# MOTOR_CONTROL.net
KiCad netlist of a schematic drawn in Altium Designer
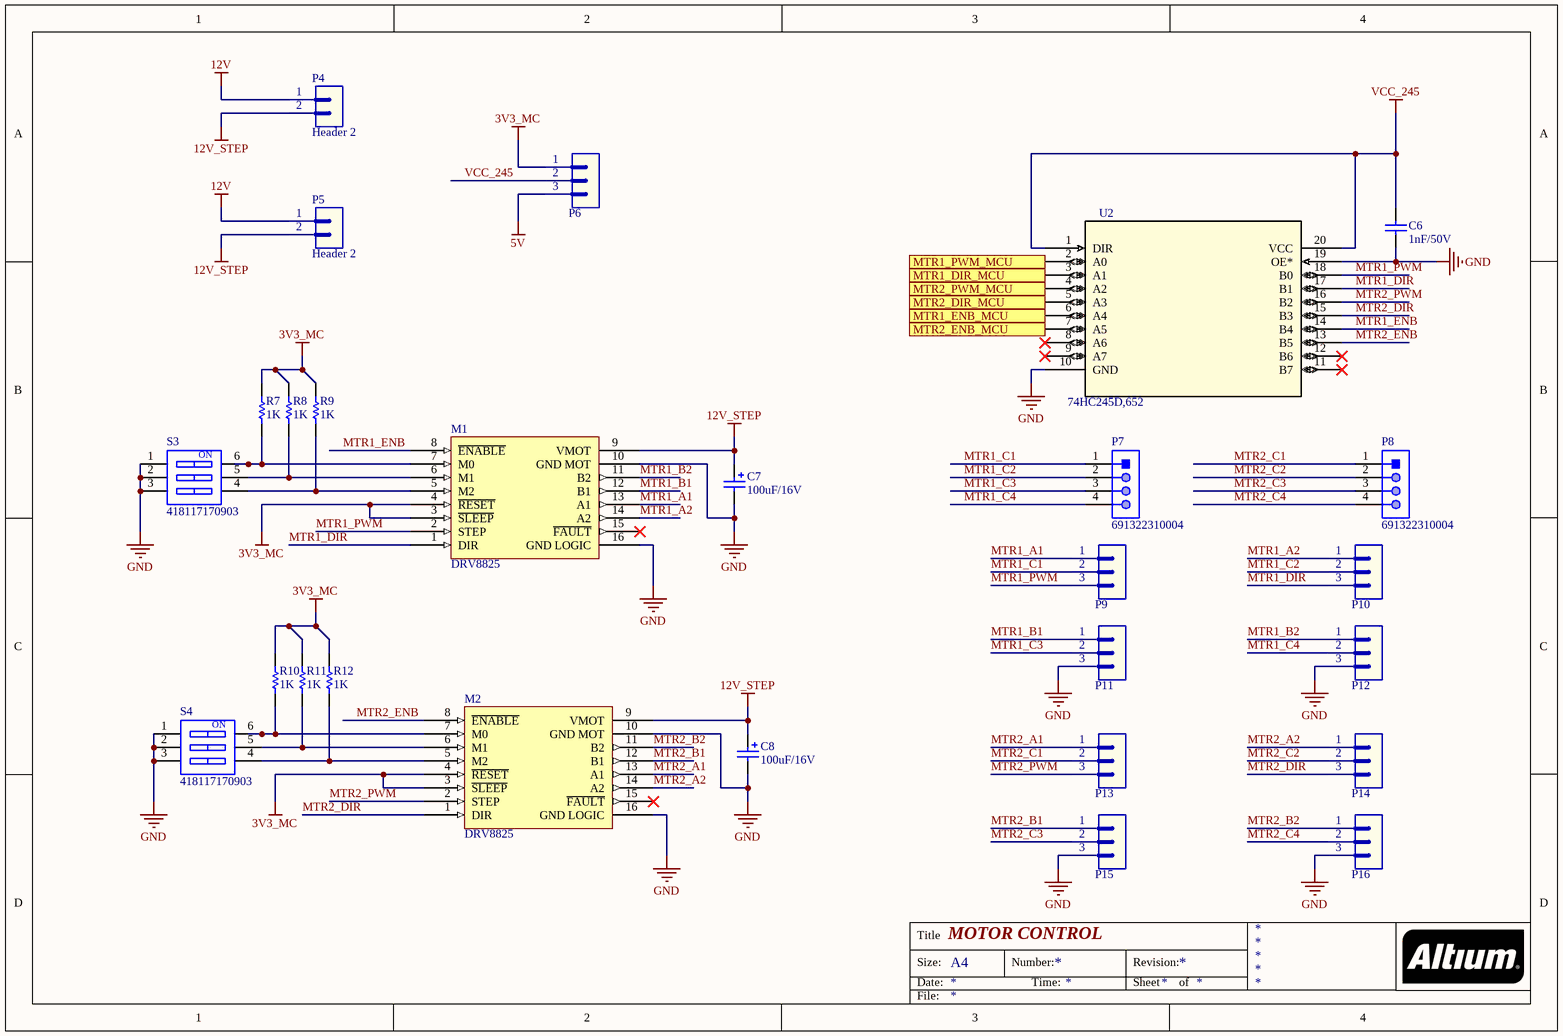
[diagram p0: MOTOR_CONTROL.SchDoc]

(export (version "E")
  (design (tool "Eeschema 10.0.6"))
  (components
    (comp (ref "C6")
      (value "1nF/50V")
      (footprint "CAP-SM-0805")
      (description "CAP CER 1000PF 100V X7R 0805")
      (fields
        (field (name "MANUFACTURER") "Johanson Dielectrics Inc.")
        (field (name "MANUFACTURER PART NUMBER") "101X15W102MV4E")
      )
      (libsource (lib "PIF_ROBOT") (part "Cap-1nF-50V-0805"))
    )
    (comp (ref "C7")
      (value "100uF/16V")
      (footprint "CAP_SM_TAN")
      (fields
        (field (name "MANUFACTURER") "Nichicon")
        (field (name "MANUFACTURER PART NUMBER") "UWX1C101MCL1GB")
        (field (name "Comment") "TAJB107M006RNJ")
      )
      (libsource (lib "PIF_ROBOT") (part "Cap-Tan-100uF-16V"))
    )
    (comp (ref "C8")
      (value "100uF/16V")
      (footprint "CAP_SM_TAN")
      (fields
        (field (name "MANUFACTURER") "Nichicon")
        (field (name "MANUFACTURER PART NUMBER") "UWX1C101MCL1GB")
        (field (name "Comment") "TAJB107M006RNJ")
      )
      (libsource (lib "PIF_ROBOT") (part "Cap-Tan-100uF-16V"))
    )
    (comp (ref "M1") (value "DRV8825") (footprint "DRV8825") (libsource (lib "PIF_ROBOT") (part "DRV8825")))
    (comp (ref "M2") (value "DRV8825") (footprint "DRV8825") (libsource (lib "PIF_ROBOT") (part "DRV8825")))
    (comp (ref "P4")
      (value "Header 2")
      (footprint "JP2")
      (description "Header, 2-Pin")
      (fields (field (name "PUBLISHER") "Altium Limited"))
      (libsource (lib "PIF_ROBOT") (part "Header 2"))
    )
    (comp (ref "P5")
      (value "Header 2")
      (footprint "JP2")
      (description "Header, 2-Pin")
      (fields (field (name "PUBLISHER") "Altium Limited"))
      (libsource (lib "PIF_ROBOT") (part "Header 2"))
    )
    (comp (ref "P6")
      (value "Header 3")
      (footprint "JP3")
      (description "Header, 3-Pin")
      (fields (field (name "PUBLISHER") "Altium Limited"))
      (libsource (lib "PIF_ROBOT") (part "Header 3"))
    )
    (comp (ref "P7")
      (value "691322310004")
      (footprint "691322310004")
      (description "WR-TBL Serie 322 Horizontal PCB Header, Pluggable, pitch 3.81mm, 4p")
      (fields (field (name "PUBLISHER") "Wurth Elektronik"))
      (libsource (lib "PIF_ROBOT") (part "691322310004"))
    )
    (comp (ref "P8")
      (value "691322310004")
      (footprint "691322310004")
      (description "WR-TBL Serie 322 Horizontal PCB Header, Pluggable, pitch 3.81mm, 4p")
      (fields (field (name "PUBLISHER") "Wurth Elektronik"))
      (libsource (lib "PIF_ROBOT") (part "691322310004"))
    )
    (comp (ref "P9")
      (value "Header 3")
      (footprint "JP3")
      (description "Header, 3-Pin")
      (fields (field (name "PUBLISHER") "Altium Limited"))
      (libsource (lib "PIF_ROBOT") (part "Header 3"))
    )
    (comp (ref "P10")
      (value "Header 3")
      (footprint "JP3")
      (description "Header, 3-Pin")
      (fields (field (name "PUBLISHER") "Altium Limited"))
      (libsource (lib "PIF_ROBOT") (part "Header 3"))
    )
    (comp (ref "P11")
      (value "Header 3")
      (footprint "JP3")
      (description "Header, 3-Pin")
      (fields (field (name "PUBLISHER") "Altium Limited"))
      (libsource (lib "PIF_ROBOT") (part "Header 3"))
    )
    (comp (ref "P12")
      (value "Header 3")
      (footprint "JP3")
      (description "Header, 3-Pin")
      (fields (field (name "PUBLISHER") "Altium Limited"))
      (libsource (lib "PIF_ROBOT") (part "Header 3"))
    )
    (comp (ref "P13")
      (value "Header 3")
      (footprint "JP3")
      (description "Header, 3-Pin")
      (fields (field (name "PUBLISHER") "Altium Limited"))
      (libsource (lib "PIF_ROBOT") (part "Header 3"))
    )
    (comp (ref "P14")
      (value "Header 3")
      (footprint "JP3")
      (description "Header, 3-Pin")
      (fields (field (name "PUBLISHER") "Altium Limited"))
      (libsource (lib "PIF_ROBOT") (part "Header 3"))
    )
    (comp (ref "P15")
      (value "Header 3")
      (footprint "JP3")
      (description "Header, 3-Pin")
      (fields (field (name "PUBLISHER") "Altium Limited"))
      (libsource (lib "PIF_ROBOT") (part "Header 3"))
    )
    (comp (ref "P16")
      (value "Header 3")
      (footprint "JP3")
      (description "Header, 3-Pin")
      (fields (field (name "PUBLISHER") "Altium Limited"))
      (libsource (lib "PIF_ROBOT") (part "Header 3"))
    )
    (comp (ref "R7")
      (value "1K")
      (footprint "RES-SM-0805")
      (description "RES 0 OHM JUMPER 0805")
      (fields
        (field (name "MANUFACTURER") "Vishay Dale")
        (field (name "MANUFACTURER PART NUMBER") "WSL080500000ZEA9")
      )
      (libsource (lib "PIF_ROBOT") (part "Res-0-0805"))
    )
    (comp (ref "R8")
      (value "1K")
      (footprint "RES-SM-0805")
      (description "RES 0 OHM JUMPER 0805")
      (fields
        (field (name "MANUFACTURER") "Vishay Dale")
        (field (name "MANUFACTURER PART NUMBER") "WSL080500000ZEA9")
      )
      (libsource (lib "PIF_ROBOT") (part "Res-0-0805"))
    )
    (comp (ref "R9")
      (value "1K")
      (footprint "RES-SM-0805")
      (description "RES 0 OHM JUMPER 0805")
      (fields
        (field (name "MANUFACTURER") "Vishay Dale")
        (field (name "MANUFACTURER PART NUMBER") "WSL080500000ZEA9")
      )
      (libsource (lib "PIF_ROBOT") (part "Res-0-0805"))
    )
    (comp (ref "R10")
      (value "1K")
      (footprint "RES-SM-0805")
      (description "RES 0 OHM JUMPER 0805")
      (fields
        (field (name "MANUFACTURER") "Vishay Dale")
        (field (name "MANUFACTURER PART NUMBER") "WSL080500000ZEA9")
      )
      (libsource (lib "PIF_ROBOT") (part "Res-0-0805"))
    )
    (comp (ref "R11")
      (value "1K")
      (footprint "RES-SM-0805")
      (description "RES 0 OHM JUMPER 0805")
      (fields
        (field (name "MANUFACTURER") "Vishay Dale")
        (field (name "MANUFACTURER PART NUMBER") "WSL080500000ZEA9")
      )
      (libsource (lib "PIF_ROBOT") (part "Res-0-0805"))
    )
    (comp (ref "R12")
      (value "1K")
      (footprint "RES-SM-0805")
      (description "RES 0 OHM JUMPER 0805")
      (fields
        (field (name "MANUFACTURER") "Vishay Dale")
        (field (name "MANUFACTURER PART NUMBER") "WSL080500000ZEA9")
      )
      (libsource (lib "PIF_ROBOT") (part "Res-0-0805"))
    )
    (comp (ref "S3")
      (value "418117170903")
      (footprint "418117170903")
      (description "WS-DITV Compact THT Dip Switch, Flat Actuator, pitch 2.54mm, 3p")
      (fields (field (name "PUBLISHER") "Wurth Elektronik"))
      (libsource (lib "PIF_ROBOT") (part "418117170903"))
    )
    (comp (ref "S4")
      (value "418117170903")
      (footprint "418117170903")
      (description "WS-DITV Compact THT Dip Switch, Flat Actuator, pitch 2.54mm, 3p")
      (fields (field (name "PUBLISHER") "Wurth Elektronik"))
      (libsource (lib "PIF_ROBOT") (part "418117170903"))
    )
    (comp (ref "U2")
      (value "74HC245D,652")
      (footprint "74hc245d")
      (description "No Description Available")
      (fields (field (name "COPYRIGHT") "Copyright (C) 2016 Accelerated Designs. All rights reserved"))
      (libsource (lib "PIF_ROBOT") (part "74HC245D,652"))
    )
  )
  (nets
    (net (code "1") (name "/MTR1_A1") (class "Default")
      (node (ref "M1") (pin "13") (pinfunction "A1_13") (pintype "output"))
      (node (ref "P9") (pin "1") (pinfunction "1_1") (pintype "passive"))
    )
    (net (code "2") (name "/MTR1_A2") (class "Default")
      (node (ref "M1") (pin "14") (pinfunction "A2_14") (pintype "output"))
      (node (ref "P10") (pin "1") (pinfunction "1_1") (pintype "passive"))
    )
    (net (code "3") (name "/MTR1_B1") (class "Default")
      (node (ref "M1") (pin "12") (pinfunction "B1_12") (pintype "output"))
      (node (ref "P11") (pin "1") (pinfunction "1_1") (pintype "passive"))
    )
    (net (code "4") (name "/MTR1_B2") (class "Default")
      (node (ref "M1") (pin "11") (pinfunction "B2_11") (pintype "output"))
      (node (ref "P12") (pin "1") (pinfunction "1_1") (pintype "passive"))
    )
    (net (code "5") (name "/MTR1_C1") (class "Default")
      (node (ref "P7") (pin "1") (pinfunction "1_1") (pintype "passive"))
      (node (ref "P9") (pin "2") (pinfunction "2_2") (pintype "passive"))
    )
    (net (code "6") (name "/MTR1_C2") (class "Default")
      (node (ref "P10") (pin "2") (pinfunction "2_2") (pintype "passive"))
      (node (ref "P7") (pin "2") (pinfunction "2_2") (pintype "passive"))
    )
    (net (code "7") (name "/MTR1_C3") (class "Default")
      (node (ref "P11") (pin "2") (pinfunction "2_2") (pintype "passive"))
      (node (ref "P7") (pin "3") (pinfunction "3_3") (pintype "passive"))
    )
    (net (code "8") (name "/MTR1_C4") (class "Default")
      (node (ref "P12") (pin "2") (pinfunction "2_2") (pintype "passive"))
      (node (ref "P7") (pin "4") (pinfunction "4_4") (pintype "passive"))
    )
    (net (code "9") (name "/MTR1_DIR") (class "Default")
      (node (ref "M1") (pin "1") (pinfunction "DIR_1") (pintype "input"))
      (node (ref "P10") (pin "3") (pinfunction "3_3") (pintype "passive"))
      (node (ref "U2") (pin "17") (pinfunction "B1_17") (pintype "bidirectional"))
    )
    (net (code "10") (name "/MTR1_DIR_MCU") (class "Default")
      (node (ref "U2") (pin "3") (pinfunction "A1_3") (pintype "bidirectional"))
    )
    (net (code "11") (name "/MTR1_ENB") (class "Default")
      (node (ref "M1") (pin "8") (pinfunction "~{ENABLE}_8") (pintype "input"))
      (node (ref "U2") (pin "14") (pinfunction "B4_14") (pintype "bidirectional"))
    )
    (net (code "12") (name "/MTR1_ENB_MCU") (class "Default")
      (node (ref "U2") (pin "6") (pinfunction "A4_6") (pintype "bidirectional"))
    )
    (net (code "13") (name "/MTR1_PWM") (class "Default")
      (node (ref "M1") (pin "2") (pinfunction "STEP_2") (pintype "input"))
      (node (ref "P9") (pin "3") (pinfunction "3_3") (pintype "passive"))
      (node (ref "U2") (pin "18") (pinfunction "B0_18") (pintype "bidirectional"))
    )
    (net (code "14") (name "/MTR1_PWM_MCU") (class "Default")
      (node (ref "U2") (pin "2") (pinfunction "A0_2") (pintype "bidirectional"))
    )
    (net (code "15") (name "/MTR2_A1") (class "Default")
      (node (ref "M2") (pin "13") (pinfunction "A1_13") (pintype "output"))
      (node (ref "P13") (pin "1") (pinfunction "1_1") (pintype "passive"))
    )
    (net (code "16") (name "/MTR2_A2") (class "Default")
      (node (ref "M2") (pin "14") (pinfunction "A2_14") (pintype "output"))
      (node (ref "P14") (pin "1") (pinfunction "1_1") (pintype "passive"))
    )
    (net (code "17") (name "/MTR2_B1") (class "Default")
      (node (ref "M2") (pin "12") (pinfunction "B1_12") (pintype "output"))
      (node (ref "P15") (pin "1") (pinfunction "1_1") (pintype "passive"))
    )
    (net (code "18") (name "/MTR2_B2") (class "Default")
      (node (ref "M2") (pin "11") (pinfunction "B2_11") (pintype "output"))
      (node (ref "P16") (pin "1") (pinfunction "1_1") (pintype "passive"))
    )
    (net (code "19") (name "/MTR2_C1") (class "Default")
      (node (ref "P13") (pin "2") (pinfunction "2_2") (pintype "passive"))
      (node (ref "P8") (pin "1") (pinfunction "1_1") (pintype "passive"))
    )
    (net (code "20") (name "/MTR2_C2") (class "Default")
      (node (ref "P14") (pin "2") (pinfunction "2_2") (pintype "passive"))
      (node (ref "P8") (pin "2") (pinfunction "2_2") (pintype "passive"))
    )
    (net (code "21") (name "/MTR2_C3") (class "Default")
      (node (ref "P15") (pin "2") (pinfunction "2_2") (pintype "passive"))
      (node (ref "P8") (pin "3") (pinfunction "3_3") (pintype "passive"))
    )
    (net (code "22") (name "/MTR2_C4") (class "Default")
      (node (ref "P16") (pin "2") (pinfunction "2_2") (pintype "passive"))
      (node (ref "P8") (pin "4") (pinfunction "4_4") (pintype "passive"))
    )
    (net (code "23") (name "/MTR2_DIR") (class "Default")
      (node (ref "M2") (pin "1") (pinfunction "DIR_1") (pintype "input"))
      (node (ref "P14") (pin "3") (pinfunction "3_3") (pintype "passive"))
      (node (ref "U2") (pin "15") (pinfunction "B3_15") (pintype "bidirectional"))
    )
    (net (code "24") (name "/MTR2_DIR_MCU") (class "Default")
      (node (ref "U2") (pin "5") (pinfunction "A3_5") (pintype "bidirectional"))
    )
    (net (code "25") (name "/MTR2_ENB") (class "Default")
      (node (ref "M2") (pin "8") (pinfunction "~{ENABLE}_8") (pintype "input"))
      (node (ref "U2") (pin "13") (pinfunction "B5_13") (pintype "bidirectional"))
    )
    (net (code "26") (name "/MTR2_ENB_MCU") (class "Default")
      (node (ref "U2") (pin "7") (pinfunction "A5_7") (pintype "bidirectional"))
    )
    (net (code "27") (name "/MTR2_PWM") (class "Default")
      (node (ref "M2") (pin "2") (pinfunction "STEP_2") (pintype "input"))
      (node (ref "P13") (pin "3") (pinfunction "3_3") (pintype "passive"))
      (node (ref "U2") (pin "16") (pinfunction "B2_16") (pintype "bidirectional"))
    )
    (net (code "28") (name "/MTR2_PWM_MCU") (class "Default")
      (node (ref "U2") (pin "4") (pinfunction "A2_4") (pintype "bidirectional"))
    )
    (net (code "29") (name "3V3_MC") (class "Default")
      (node (ref "M1") (pin "3") (pinfunction "~{SLEEP}_3") (pintype "input"))
      (node (ref "M1") (pin "4") (pinfunction "~{RESET}_4") (pintype "input"))
      (node (ref "M2") (pin "3") (pinfunction "~{SLEEP}_3") (pintype "input"))
      (node (ref "M2") (pin "4") (pinfunction "~{RESET}_4") (pintype "input"))
      (node (ref "P6") (pin "1") (pinfunction "1_1") (pintype "passive"))
      (node (ref "R10") (pin "2") (pinfunction "2_2") (pintype "passive"))
      (node (ref "R11") (pin "2") (pinfunction "2_2") (pintype "passive"))
      (node (ref "R12") (pin "2") (pinfunction "2_2") (pintype "passive"))
      (node (ref "R7") (pin "2") (pinfunction "2_2") (pintype "passive"))
      (node (ref "R8") (pin "2") (pinfunction "2_2") (pintype "passive"))
      (node (ref "R9") (pin "2") (pinfunction "2_2") (pintype "passive"))
    )
    (net (code "30") (name "5V") (class "Default")
      (node (ref "P6") (pin "3") (pinfunction "3_3") (pintype "passive"))
    )
    (net (code "31") (name "12V") (class "Default")
      (node (ref "P4") (pin "1") (pinfunction "1_1") (pintype "passive"))
      (node (ref "P5") (pin "1") (pinfunction "1_1") (pintype "passive"))
    )
    (net (code "32") (name "12V_STEP") (class "Default")
      (node (ref "C7") (pin "1") (pinfunction "1_1") (pintype "passive"))
      (node (ref "C8") (pin "1") (pinfunction "1_1") (pintype "passive"))
      (node (ref "M1") (pin "9") (pinfunction "VMOT_9") (pintype "passive"))
      (node (ref "M2") (pin "9") (pinfunction "VMOT_9") (pintype "passive"))
      (node (ref "P4") (pin "2") (pinfunction "2_2") (pintype "passive"))
      (node (ref "P5") (pin "2") (pinfunction "2_2") (pintype "passive"))
    )
    (net (code "33") (name "GND") (class "Default")
      (node (ref "C6") (pin "2") (pinfunction "2_2") (pintype "passive"))
      (node (ref "C7") (pin "2") (pinfunction "2_2") (pintype "passive"))
      (node (ref "C8") (pin "2") (pinfunction "2_2") (pintype "passive"))
      (node (ref "M1") (pin "10") (pinfunction "GND_MOT_10") (pintype "passive"))
      (node (ref "M1") (pin "16") (pinfunction "GND_LOGIC_16") (pintype "passive"))
      (node (ref "M2") (pin "10") (pinfunction "GND_MOT_10") (pintype "passive"))
      (node (ref "M2") (pin "16") (pinfunction "GND_LOGIC_16") (pintype "passive"))
      (node (ref "P11") (pin "3") (pinfunction "3_3") (pintype "passive"))
      (node (ref "P12") (pin "3") (pinfunction "3_3") (pintype "passive"))
      (node (ref "P15") (pin "3") (pinfunction "3_3") (pintype "passive"))
      (node (ref "P16") (pin "3") (pinfunction "3_3") (pintype "passive"))
      (node (ref "S3") (pin "1") (pinfunction "1_1") (pintype "passive"))
      (node (ref "S3") (pin "2") (pinfunction "2_2") (pintype "passive"))
      (node (ref "S3") (pin "3") (pinfunction "3_3") (pintype "passive"))
      (node (ref "S4") (pin "1") (pinfunction "1_1") (pintype "passive"))
      (node (ref "S4") (pin "2") (pinfunction "2_2") (pintype "passive"))
      (node (ref "S4") (pin "3") (pinfunction "3_3") (pintype "passive"))
      (node (ref "U2") (pin "10") (pinfunction "GND_10") (pintype "power_in"))
      (node (ref "U2") (pin "19") (pinfunction "OE*_19") (pintype "input"))
    )
    (net (code "34") (name "Net-(M1-M0)") (class "Default")
      (node (ref "M1") (pin "7") (pinfunction "M0_7") (pintype "input"))
      (node (ref "R7") (pin "1") (pinfunction "1_1") (pintype "passive"))
      (node (ref "S3") (pin "6") (pinfunction "6_6") (pintype "passive"))
    )
    (net (code "35") (name "Net-(M1-M1)") (class "Default")
      (node (ref "M1") (pin "6") (pinfunction "M1_6") (pintype "input"))
      (node (ref "R8") (pin "1") (pinfunction "1_1") (pintype "passive"))
      (node (ref "S3") (pin "5") (pinfunction "5_5") (pintype "passive"))
    )
    (net (code "36") (name "Net-(M1-M2)") (class "Default")
      (node (ref "M1") (pin "5") (pinfunction "M2_5") (pintype "input"))
      (node (ref "R9") (pin "1") (pinfunction "1_1") (pintype "passive"))
      (node (ref "S3") (pin "4") (pinfunction "4_4") (pintype "passive"))
    )
    (net (code "37") (name "Net-(M2-M0)") (class "Default")
      (node (ref "M2") (pin "7") (pinfunction "M0_7") (pintype "input"))
      (node (ref "R10") (pin "1") (pinfunction "1_1") (pintype "passive"))
      (node (ref "S4") (pin "6") (pinfunction "6_6") (pintype "passive"))
    )
    (net (code "38") (name "Net-(M2-M1)") (class "Default")
      (node (ref "M2") (pin "6") (pinfunction "M1_6") (pintype "input"))
      (node (ref "R11") (pin "1") (pinfunction "1_1") (pintype "passive"))
      (node (ref "S4") (pin "5") (pinfunction "5_5") (pintype "passive"))
    )
    (net (code "39") (name "Net-(M2-M2)") (class "Default")
      (node (ref "M2") (pin "5") (pinfunction "M2_5") (pintype "input"))
      (node (ref "R12") (pin "1") (pinfunction "1_1") (pintype "passive"))
      (node (ref "S4") (pin "4") (pinfunction "4_4") (pintype "passive"))
    )
    (net (code "40") (name "VCC_245") (class "Default")
      (node (ref "C6") (pin "1") (pinfunction "1_1") (pintype "passive"))
      (node (ref "P6") (pin "2") (pinfunction "2_2") (pintype "passive"))
      (node (ref "U2") (pin "1") (pinfunction "DIR_1") (pintype "input"))
      (node (ref "U2") (pin "20") (pinfunction "VCC_20") (pintype "power_in"))
    )
    (net (code "41") (name "unconnected-(M1-~{FAULT}-Pad15)") (class "Default")
      (node (ref "M1") (pin "15") (pinfunction "~{FAULT}_15") (pintype "output+no_connect"))
    )
    (net (code "42") (name "unconnected-(M2-~{FAULT}-Pad15)") (class "Default")
      (node (ref "M2") (pin "15") (pinfunction "~{FAULT}_15") (pintype "output+no_connect"))
    )
    (net (code "43") (name "unconnected-(U2-A6-Pad8)") (class "Default")
      (node (ref "U2") (pin "8") (pinfunction "A6_8") (pintype "bidirectional+no_connect"))
    )
    (net (code "44") (name "unconnected-(U2-A7-Pad9)") (class "Default")
      (node (ref "U2") (pin "9") (pinfunction "A7_9") (pintype "bidirectional+no_connect"))
    )
    (net (code "45") (name "unconnected-(U2-B6-Pad12)") (class "Default")
      (node (ref "U2") (pin "12") (pinfunction "B6_12") (pintype "bidirectional+no_connect"))
    )
    (net (code "46") (name "unconnected-(U2-B7-Pad11)") (class "Default")
      (node (ref "U2") (pin "11") (pinfunction "B7_11") (pintype "bidirectional+no_connect"))
    )
  )
)
